# DEVICE.net
KiCad netlist of a schematic drawn in Altium Designer
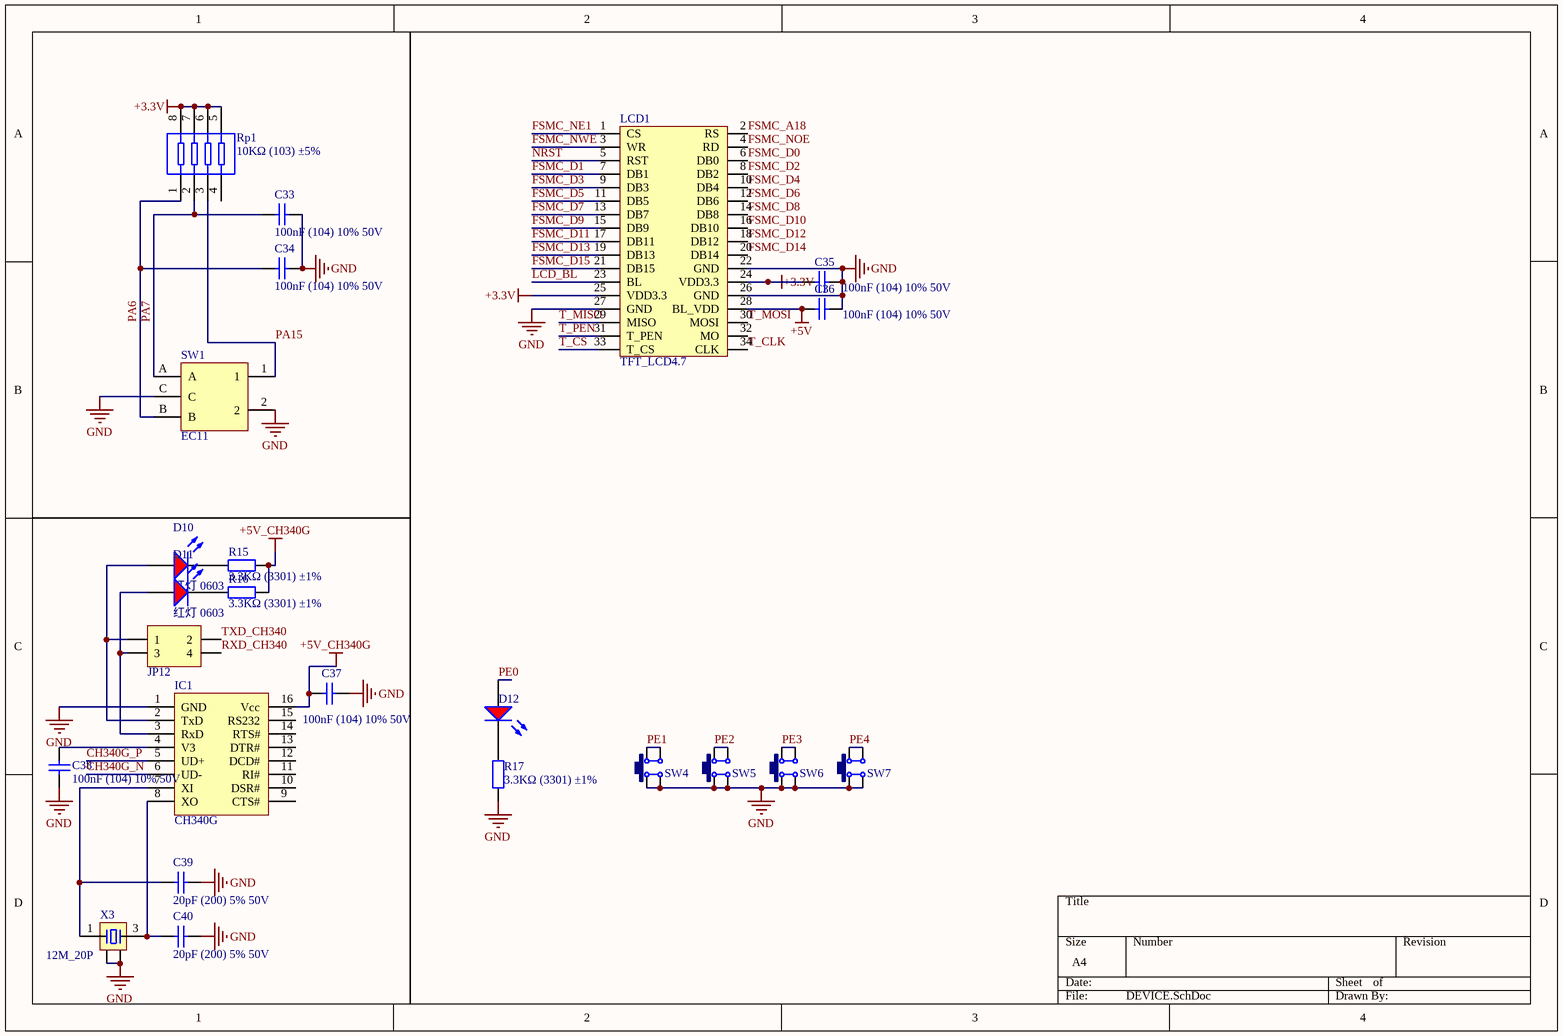
[diagram p0: DEVICE.SchDoc]

(export (version "E")
  (design (tool "Eeschema 10.0.6"))
  (components
    (comp (ref "C33")
      (value "100nF (104) 10% 50V")
      (footprint "0603_C")
      (description "贴片电容")
      (libsource (lib "Cap") (part "0603 100nF (104) 10% 50V"))
    )
    (comp (ref "C34")
      (value "100nF (104) 10% 50V")
      (footprint "0603_C")
      (description "贴片电容")
      (libsource (lib "Cap") (part "0603 100nF (104) 10% 50V"))
    )
    (comp (ref "C35")
      (value "100nF (104) 10% 50V")
      (footprint "0603_C")
      (description "贴片电容")
      (libsource (lib "Cap") (part "0603 100nF (104) 10% 50V"))
    )
    (comp (ref "C36")
      (value "100nF (104) 10% 50V")
      (footprint "0603_C")
      (description "贴片电容")
      (libsource (lib "Cap") (part "0603 100nF (104) 10% 50V"))
    )
    (comp (ref "C37")
      (value "100nF (104) 10% 50V")
      (footprint "0603_C")
      (description "贴片电容")
      (libsource (lib "Cap") (part "0603 100nF (104) 10% 50V"))
    )
    (comp (ref "C38")
      (value "100nF (104) 10% 50V")
      (footprint "0603_C")
      (description "贴片电容")
      (libsource (lib "Cap") (part "0603 100nF (104) 10% 50V"))
    )
    (comp (ref "C39")
      (value "20pF (200) 5% 50V")
      (footprint "0603_C")
      (description "贴片电容")
      (libsource (lib "Cap") (part "0603 20pF (200) 5% 50V"))
    )
    (comp (ref "C40")
      (value "20pF (200) 5% 50V")
      (footprint "0603_C")
      (description "贴片电容")
      (libsource (lib "Cap") (part "0603 20pF (200) 5% 50V"))
    )
    (comp (ref "D10")
      (value "红灯 0603")
      (footprint "0603_LED_S1")
      (description "发光二极管")
      (libsource (lib "LED") (part "0603 红灯"))
    )
    (comp (ref "D11")
      (value "红灯 0603")
      (footprint "0603_LED_S1")
      (description "发光二极管")
      (libsource (lib "LED") (part "0603 红灯"))
    )
    (comp (ref "D12")
      (value "红灯 0603")
      (footprint "0603_LED_S1")
      (description "发光二极管")
      (libsource (lib "LED") (part "0603 红灯"))
    )
    (comp (ref "IC1")
      (value "CH340G")
      (footprint "SOP16_L")
      (description "串口转USB")
      (fields (field (name "版权归属") "源创客"))
      (libsource (lib "1.1   - IC芯片") (part "CH340G"))
    )
    (comp (ref "JP12")
      (value "Header2X2")
      (footprint "HDR2.54-LI-2x2P")
      (description "2*2P接插件")
      (fields (field (name "版权归属") "源创客"))
      (libsource (lib "4.5   - 接插件-脚距2.54") (part "Header 2X2"))
    )
    (comp (ref "LCD1")
      (value "TFT_LCD4.7")
      (footprint "DB2*17-3.5")
      (libsource (lib "STM32F407Z") (part "TFT_LCD4.7"))
    )
    (comp (ref "R15")
      (value "3.3KΩ (3301) ±1%")
      (footprint "0603_R")
      (description "贴片电阻")
      (libsource (lib "RES") (part "0603 3.3KΩ (3301) 1%"))
    )
    (comp (ref "R16")
      (value "3.3KΩ (3301) ±1%")
      (footprint "0603_R")
      (description "贴片电阻")
      (libsource (lib "RES") (part "0603 3.3KΩ (3301) 1%"))
    )
    (comp (ref "R17")
      (value "3.3KΩ (3301) ±1%")
      (footprint "0603_R")
      (description "贴片电阻")
      (libsource (lib "") (part "0603 3.3KΩ (3301) 1%_1"))
    )
    (comp (ref "Rp1")
      (value "10KΩ (103) ±5%")
      (footprint "0603_Rx4")
      (description "贴片排阻")
      (libsource (lib "RES") (part "0603*4  10KΩ (103) 5%"))
    )
    (comp (ref "SW1")
      (value "EC11")
      (footprint "EC11-B")
      (description "数字开关编码器")
      (fields (field (name "版权归属") "源创客"))
      (libsource (lib "5.1   - 按键-开关") (part "EC11"))
    )
    (comp (ref "SW4")
      (value "6x6x5")
      (footprint "TSW DIP-6*6*6")
      (description "直插6x6轻触开关")
      (fields (field (name "版权归属") "源创客"))
      (libsource (lib "按键-开关") (part "TSW DIP-6x6"))
    )
    (comp (ref "SW5")
      (value "6x6x5")
      (footprint "TSW DIP-6*6*6")
      (description "直插6x6轻触开关")
      (fields (field (name "版权归属") "源创客"))
      (libsource (lib "按键-开关") (part "TSW DIP-6x6"))
    )
    (comp (ref "SW6")
      (value "6x6x5")
      (footprint "TSW DIP-6*6*6")
      (description "直插6x6轻触开关")
      (fields (field (name "版权归属") "源创客"))
      (libsource (lib "按键-开关") (part "TSW DIP-6x6"))
    )
    (comp (ref "SW7")
      (value "6x6x5")
      (footprint "TSW DIP-6*6*6")
      (description "直插6x6轻触开关")
      (fields (field (name "版权归属") "源创客"))
      (libsource (lib "按键-开关") (part "TSW DIP-6x6"))
    )
    (comp (ref "X3")
      (value "12M_20P")
      (footprint "OSC 3225-4P")
      (description "4脚无源晶振")
      (fields (field (name "版权归属") "源创客"))
      (libsource (lib "10.1 - 保险丝-晶振") (part "XTAL-4P"))
    )
  )
  (nets
    (net (code "1") (name "+3.3V") (class "Default")
      (node (ref "C35") (pin "1") (pinfunction "1_1") (pintype "passive"))
      (node (ref "LCD1") (pin "24") (pinfunction "VDD3.3_24") (pintype "passive"))
      (node (ref "LCD1") (pin "25") (pinfunction "VDD3.3_25") (pintype "passive"))
      (node (ref "Rp1") (pin "5") (pinfunction "5_5") (pintype "passive"))
      (node (ref "Rp1") (pin "6") (pinfunction "6_6") (pintype "passive"))
      (node (ref "Rp1") (pin "7") (pinfunction "7_7") (pintype "passive"))
      (node (ref "Rp1") (pin "8") (pinfunction "8_8") (pintype "passive"))
    )
    (net (code "2") (name "+5V") (class "Default")
      (node (ref "C36") (pin "2") (pinfunction "2_2") (pintype "passive"))
      (node (ref "LCD1") (pin "28") (pinfunction "BL_VDD_28") (pintype "passive"))
    )
    (net (code "3") (name "+5V_CH340G") (class "Default")
      (node (ref "C37") (pin "1") (pinfunction "1_1") (pintype "passive"))
      (node (ref "IC1") (pin "16") (pinfunction "Vcc_16") (pintype "passive"))
      (node (ref "R15") (pin "2") (pinfunction "2_2") (pintype "passive"))
      (node (ref "R16") (pin "2") (pinfunction "2_2") (pintype "passive"))
    )
    (net (code "4") (name "/CH340G_N") (class "Default")
      (node (ref "IC1") (pin "6") (pinfunction "UD-_6") (pintype "passive"))
    )
    (net (code "5") (name "/CH340G_P") (class "Default")
      (node (ref "IC1") (pin "5") (pinfunction "UD+_5") (pintype "passive"))
    )
    (net (code "6") (name "/FSMC_A18") (class "Default")
      (node (ref "LCD1") (pin "2") (pinfunction "RS_2") (pintype "passive"))
    )
    (net (code "7") (name "/FSMC_D0") (class "Default")
      (node (ref "LCD1") (pin "6") (pinfunction "DB0_6") (pintype "passive"))
    )
    (net (code "8") (name "/FSMC_D1") (class "Default")
      (node (ref "LCD1") (pin "7") (pinfunction "DB1_7") (pintype "passive"))
    )
    (net (code "9") (name "/FSMC_D2") (class "Default")
      (node (ref "LCD1") (pin "8") (pinfunction "DB2_8") (pintype "passive"))
    )
    (net (code "10") (name "/FSMC_D3") (class "Default")
      (node (ref "LCD1") (pin "9") (pinfunction "DB3_9") (pintype "passive"))
    )
    (net (code "11") (name "/FSMC_D4") (class "Default")
      (node (ref "LCD1") (pin "10") (pinfunction "DB4_10") (pintype "passive"))
    )
    (net (code "12") (name "/FSMC_D5") (class "Default")
      (node (ref "LCD1") (pin "11") (pinfunction "DB5_11") (pintype "passive"))
    )
    (net (code "13") (name "/FSMC_D6") (class "Default")
      (node (ref "LCD1") (pin "12") (pinfunction "DB6_12") (pintype "passive"))
    )
    (net (code "14") (name "/FSMC_D7") (class "Default")
      (node (ref "LCD1") (pin "13") (pinfunction "DB7_13") (pintype "passive"))
    )
    (net (code "15") (name "/FSMC_D8") (class "Default")
      (node (ref "LCD1") (pin "14") (pinfunction "DB8_14") (pintype "passive"))
    )
    (net (code "16") (name "/FSMC_D9") (class "Default")
      (node (ref "LCD1") (pin "15") (pinfunction "DB9_15") (pintype "passive"))
    )
    (net (code "17") (name "/FSMC_D10") (class "Default")
      (node (ref "LCD1") (pin "16") (pinfunction "DB10_16") (pintype "passive"))
    )
    (net (code "18") (name "/FSMC_D11") (class "Default")
      (node (ref "LCD1") (pin "17") (pinfunction "DB11_17") (pintype "passive"))
    )
    (net (code "19") (name "/FSMC_D12") (class "Default")
      (node (ref "LCD1") (pin "18") (pinfunction "DB12_18") (pintype "passive"))
    )
    (net (code "20") (name "/FSMC_D13") (class "Default")
      (node (ref "LCD1") (pin "19") (pinfunction "DB13_19") (pintype "passive"))
    )
    (net (code "21") (name "/FSMC_D14") (class "Default")
      (node (ref "LCD1") (pin "20") (pinfunction "DB14_20") (pintype "passive"))
    )
    (net (code "22") (name "/FSMC_D15") (class "Default")
      (node (ref "LCD1") (pin "21") (pinfunction "DB15_21") (pintype "passive"))
    )
    (net (code "23") (name "/FSMC_NE1") (class "Default")
      (node (ref "LCD1") (pin "1") (pinfunction "CS_1") (pintype "passive"))
    )
    (net (code "24") (name "/FSMC_NOE") (class "Default")
      (node (ref "LCD1") (pin "4") (pinfunction "RD_4") (pintype "passive"))
    )
    (net (code "25") (name "/FSMC_NWE") (class "Default")
      (node (ref "LCD1") (pin "3") (pinfunction "WR_3") (pintype "passive"))
    )
    (net (code "26") (name "/LCD_BL") (class "Default")
      (node (ref "LCD1") (pin "23") (pinfunction "BL_23") (pintype "passive"))
    )
    (net (code "27") (name "/NRST") (class "Default")
      (node (ref "LCD1") (pin "5") (pinfunction "RST_5") (pintype "passive"))
    )
    (net (code "28") (name "/PA6") (class "Default")
      (node (ref "C34") (pin "2") (pinfunction "2_2") (pintype "passive"))
      (node (ref "Rp1") (pin "1") (pinfunction "1_1") (pintype "passive"))
      (node (ref "SW1") (pin "B") (pinfunction "B_B") (pintype "passive"))
    )
    (net (code "29") (name "/PA7") (class "Default")
      (node (ref "C33") (pin "2") (pinfunction "2_2") (pintype "passive"))
      (node (ref "Rp1") (pin "2") (pinfunction "2_2") (pintype "passive"))
      (node (ref "SW1") (pin "A") (pinfunction "A_A") (pintype "passive"))
    )
    (net (code "30") (name "/PA15") (class "Default")
      (node (ref "Rp1") (pin "3") (pinfunction "3_3") (pintype "passive"))
      (node (ref "SW1") (pin "1") (pinfunction "1_1") (pintype "passive"))
    )
    (net (code "31") (name "/PE0") (class "Default")
      (node (ref "D12") (pin "A") (pinfunction "A_A") (pintype "passive"))
    )
    (net (code "32") (name "/PE1") (class "Default")
      (node (ref "SW4") (pin "2") (pinfunction "2_2") (pintype "passive"))
      (node (ref "SW4") (pin "3") (pinfunction "3_3") (pintype "passive"))
    )
    (net (code "33") (name "/PE2") (class "Default")
      (node (ref "SW5") (pin "2") (pinfunction "2_2") (pintype "passive"))
      (node (ref "SW5") (pin "3") (pinfunction "3_3") (pintype "passive"))
    )
    (net (code "34") (name "/PE3") (class "Default")
      (node (ref "SW6") (pin "2") (pinfunction "2_2") (pintype "passive"))
      (node (ref "SW6") (pin "3") (pinfunction "3_3") (pintype "passive"))
    )
    (net (code "35") (name "/PE4") (class "Default")
      (node (ref "SW7") (pin "2") (pinfunction "2_2") (pintype "passive"))
      (node (ref "SW7") (pin "3") (pinfunction "3_3") (pintype "passive"))
    )
    (net (code "36") (name "/RXD_CH340") (class "Default")
      (node (ref "JP12") (pin "4") (pinfunction "4_4") (pintype "passive"))
    )
    (net (code "37") (name "/TXD_CH340") (class "Default")
      (node (ref "JP12") (pin "2") (pinfunction "2_2") (pintype "passive"))
    )
    (net (code "38") (name "/T_CLK") (class "Default")
      (node (ref "LCD1") (pin "34") (pinfunction "CLK_34") (pintype "passive"))
    )
    (net (code "39") (name "/T_CS") (class "Default")
      (node (ref "LCD1") (pin "33") (pinfunction "T_CS_33") (pintype "passive"))
    )
    (net (code "40") (name "/T_MISO") (class "Default")
      (node (ref "LCD1") (pin "29") (pinfunction "MISO_29") (pintype "passive"))
    )
    (net (code "41") (name "/T_MOSI") (class "Default")
      (node (ref "LCD1") (pin "30") (pinfunction "MOSI_30") (pintype "passive"))
    )
    (net (code "42") (name "/T_PEN") (class "Default")
      (node (ref "LCD1") (pin "31") (pinfunction "T_PEN_31") (pintype "passive"))
    )
    (net (code "43") (name "GND") (class "Default")
      (node (ref "C33") (pin "1") (pinfunction "1_1") (pintype "passive"))
      (node (ref "C34") (pin "1") (pinfunction "1_1") (pintype "passive"))
      (node (ref "C35") (pin "2") (pinfunction "2_2") (pintype "passive"))
      (node (ref "C36") (pin "1") (pinfunction "1_1") (pintype "passive"))
      (node (ref "C37") (pin "2") (pinfunction "2_2") (pintype "passive"))
      (node (ref "C38") (pin "2") (pinfunction "2_2") (pintype "passive"))
      (node (ref "C39") (pin "1") (pinfunction "1_1") (pintype "passive"))
      (node (ref "C40") (pin "1") (pinfunction "1_1") (pintype "passive"))
      (node (ref "IC1") (pin "1") (pinfunction "GND_1") (pintype "passive"))
      (node (ref "LCD1") (pin "22") (pinfunction "GND_22") (pintype "passive"))
      (node (ref "LCD1") (pin "26") (pinfunction "GND_26") (pintype "passive"))
      (node (ref "LCD1") (pin "27") (pinfunction "GND_27") (pintype "passive"))
      (node (ref "R17") (pin "1") (pinfunction "1_1") (pintype "passive"))
      (node (ref "SW1") (pin "2") (pinfunction "2_2") (pintype "passive"))
      (node (ref "SW1") (pin "C") (pinfunction "C_C") (pintype "passive"))
      (node (ref "SW4") (pin "1") (pinfunction "1_1") (pintype "passive"))
      (node (ref "SW4") (pin "4") (pinfunction "4_4") (pintype "passive"))
      (node (ref "SW5") (pin "1") (pinfunction "1_1") (pintype "passive"))
      (node (ref "SW5") (pin "4") (pinfunction "4_4") (pintype "passive"))
      (node (ref "SW6") (pin "1") (pinfunction "1_1") (pintype "passive"))
      (node (ref "SW6") (pin "4") (pinfunction "4_4") (pintype "passive"))
      (node (ref "SW7") (pin "1") (pinfunction "1_1") (pintype "passive"))
      (node (ref "SW7") (pin "4") (pinfunction "4_4") (pintype "passive"))
      (node (ref "X3") (pin "2") (pinfunction "2_2") (pintype "passive"))
      (node (ref "X3") (pin "4") (pinfunction "4_4") (pintype "passive"))
    )
    (net (code "44") (name "Net-(D10-PadK)") (class "Default")
      (node (ref "D10") (pin "K") (pinfunction "K_K") (pintype "passive"))
      (node (ref "R15") (pin "1") (pinfunction "1_1") (pintype "passive"))
    )
    (net (code "45") (name "Net-(D11-PadK)") (class "Default")
      (node (ref "D11") (pin "K") (pinfunction "K_K") (pintype "passive"))
      (node (ref "R16") (pin "1") (pinfunction "1_1") (pintype "passive"))
    )
    (net (code "46") (name "Net-(D12-PadK)") (class "Default")
      (node (ref "D12") (pin "K") (pinfunction "K_K") (pintype "passive"))
      (node (ref "R17") (pin "2") (pinfunction "2_2") (pintype "passive"))
    )
    (net (code "47") (name "Net-(IC1-RxD)") (class "Default")
      (node (ref "D11") (pin "A") (pinfunction "A_A") (pintype "passive"))
      (node (ref "IC1") (pin "3") (pinfunction "RxD_3") (pintype "passive"))
      (node (ref "JP12") (pin "3") (pinfunction "3_3") (pintype "passive"))
    )
    (net (code "48") (name "Net-(IC1-TxD)") (class "Default")
      (node (ref "D10") (pin "A") (pinfunction "A_A") (pintype "passive"))
      (node (ref "IC1") (pin "2") (pinfunction "TxD_2") (pintype "passive"))
      (node (ref "JP12") (pin "1") (pinfunction "1_1") (pintype "passive"))
    )
    (net (code "49") (name "Net-(IC1-V3)") (class "Default")
      (node (ref "C38") (pin "1") (pinfunction "1_1") (pintype "passive"))
      (node (ref "IC1") (pin "4") (pinfunction "V3_4") (pintype "passive"))
    )
    (net (code "50") (name "Net-(IC1-XI)") (class "Default")
      (node (ref "C39") (pin "2") (pinfunction "2_2") (pintype "passive"))
      (node (ref "IC1") (pin "7") (pinfunction "XI_7") (pintype "passive"))
      (node (ref "X3") (pin "1") (pinfunction "1_1") (pintype "passive"))
    )
    (net (code "51") (name "Net-(IC1-XO)") (class "Default")
      (node (ref "C40") (pin "2") (pinfunction "2_2") (pintype "passive"))
      (node (ref "IC1") (pin "8") (pinfunction "XO_8") (pintype "passive"))
      (node (ref "X3") (pin "3") (pinfunction "3_3") (pintype "passive"))
    )
    (net (code "52") (name "unconnected-(IC1-CTS#-Pad9)") (class "Default")
      (node (ref "IC1") (pin "9") (pinfunction "CTS#_9") (pintype "passive"))
    )
    (net (code "53") (name "unconnected-(IC1-DCD#-Pad12)") (class "Default")
      (node (ref "IC1") (pin "12") (pinfunction "DCD#_12") (pintype "passive"))
    )
    (net (code "54") (name "unconnected-(IC1-DSR#-Pad10)") (class "Default")
      (node (ref "IC1") (pin "10") (pinfunction "DSR#_10") (pintype "passive"))
    )
    (net (code "55") (name "unconnected-(IC1-DTR#-Pad13)") (class "Default")
      (node (ref "IC1") (pin "13") (pinfunction "DTR#_13") (pintype "passive"))
    )
    (net (code "56") (name "unconnected-(IC1-RI#-Pad11)") (class "Default")
      (node (ref "IC1") (pin "11") (pinfunction "RI#_11") (pintype "passive"))
    )
    (net (code "57") (name "unconnected-(IC1-RS232-Pad15)") (class "Default")
      (node (ref "IC1") (pin "15") (pinfunction "RS232_15") (pintype "passive"))
    )
    (net (code "58") (name "unconnected-(IC1-RTS#-Pad14)") (class "Default")
      (node (ref "IC1") (pin "14") (pinfunction "RTS#_14") (pintype "passive"))
    )
    (net (code "59") (name "unconnected-(LCD1-MO-Pad32)") (class "Default")
      (node (ref "LCD1") (pin "32") (pinfunction "MO_32") (pintype "passive"))
    )
    (net (code "60") (name "unconnected-(Rp1-Pad4)") (class "Default")
      (node (ref "Rp1") (pin "4") (pinfunction "4_4") (pintype "passive"))
    )
  )
)
